# pwm-tl494.net
KiCad netlist of a schematic drawn in Altium Designer
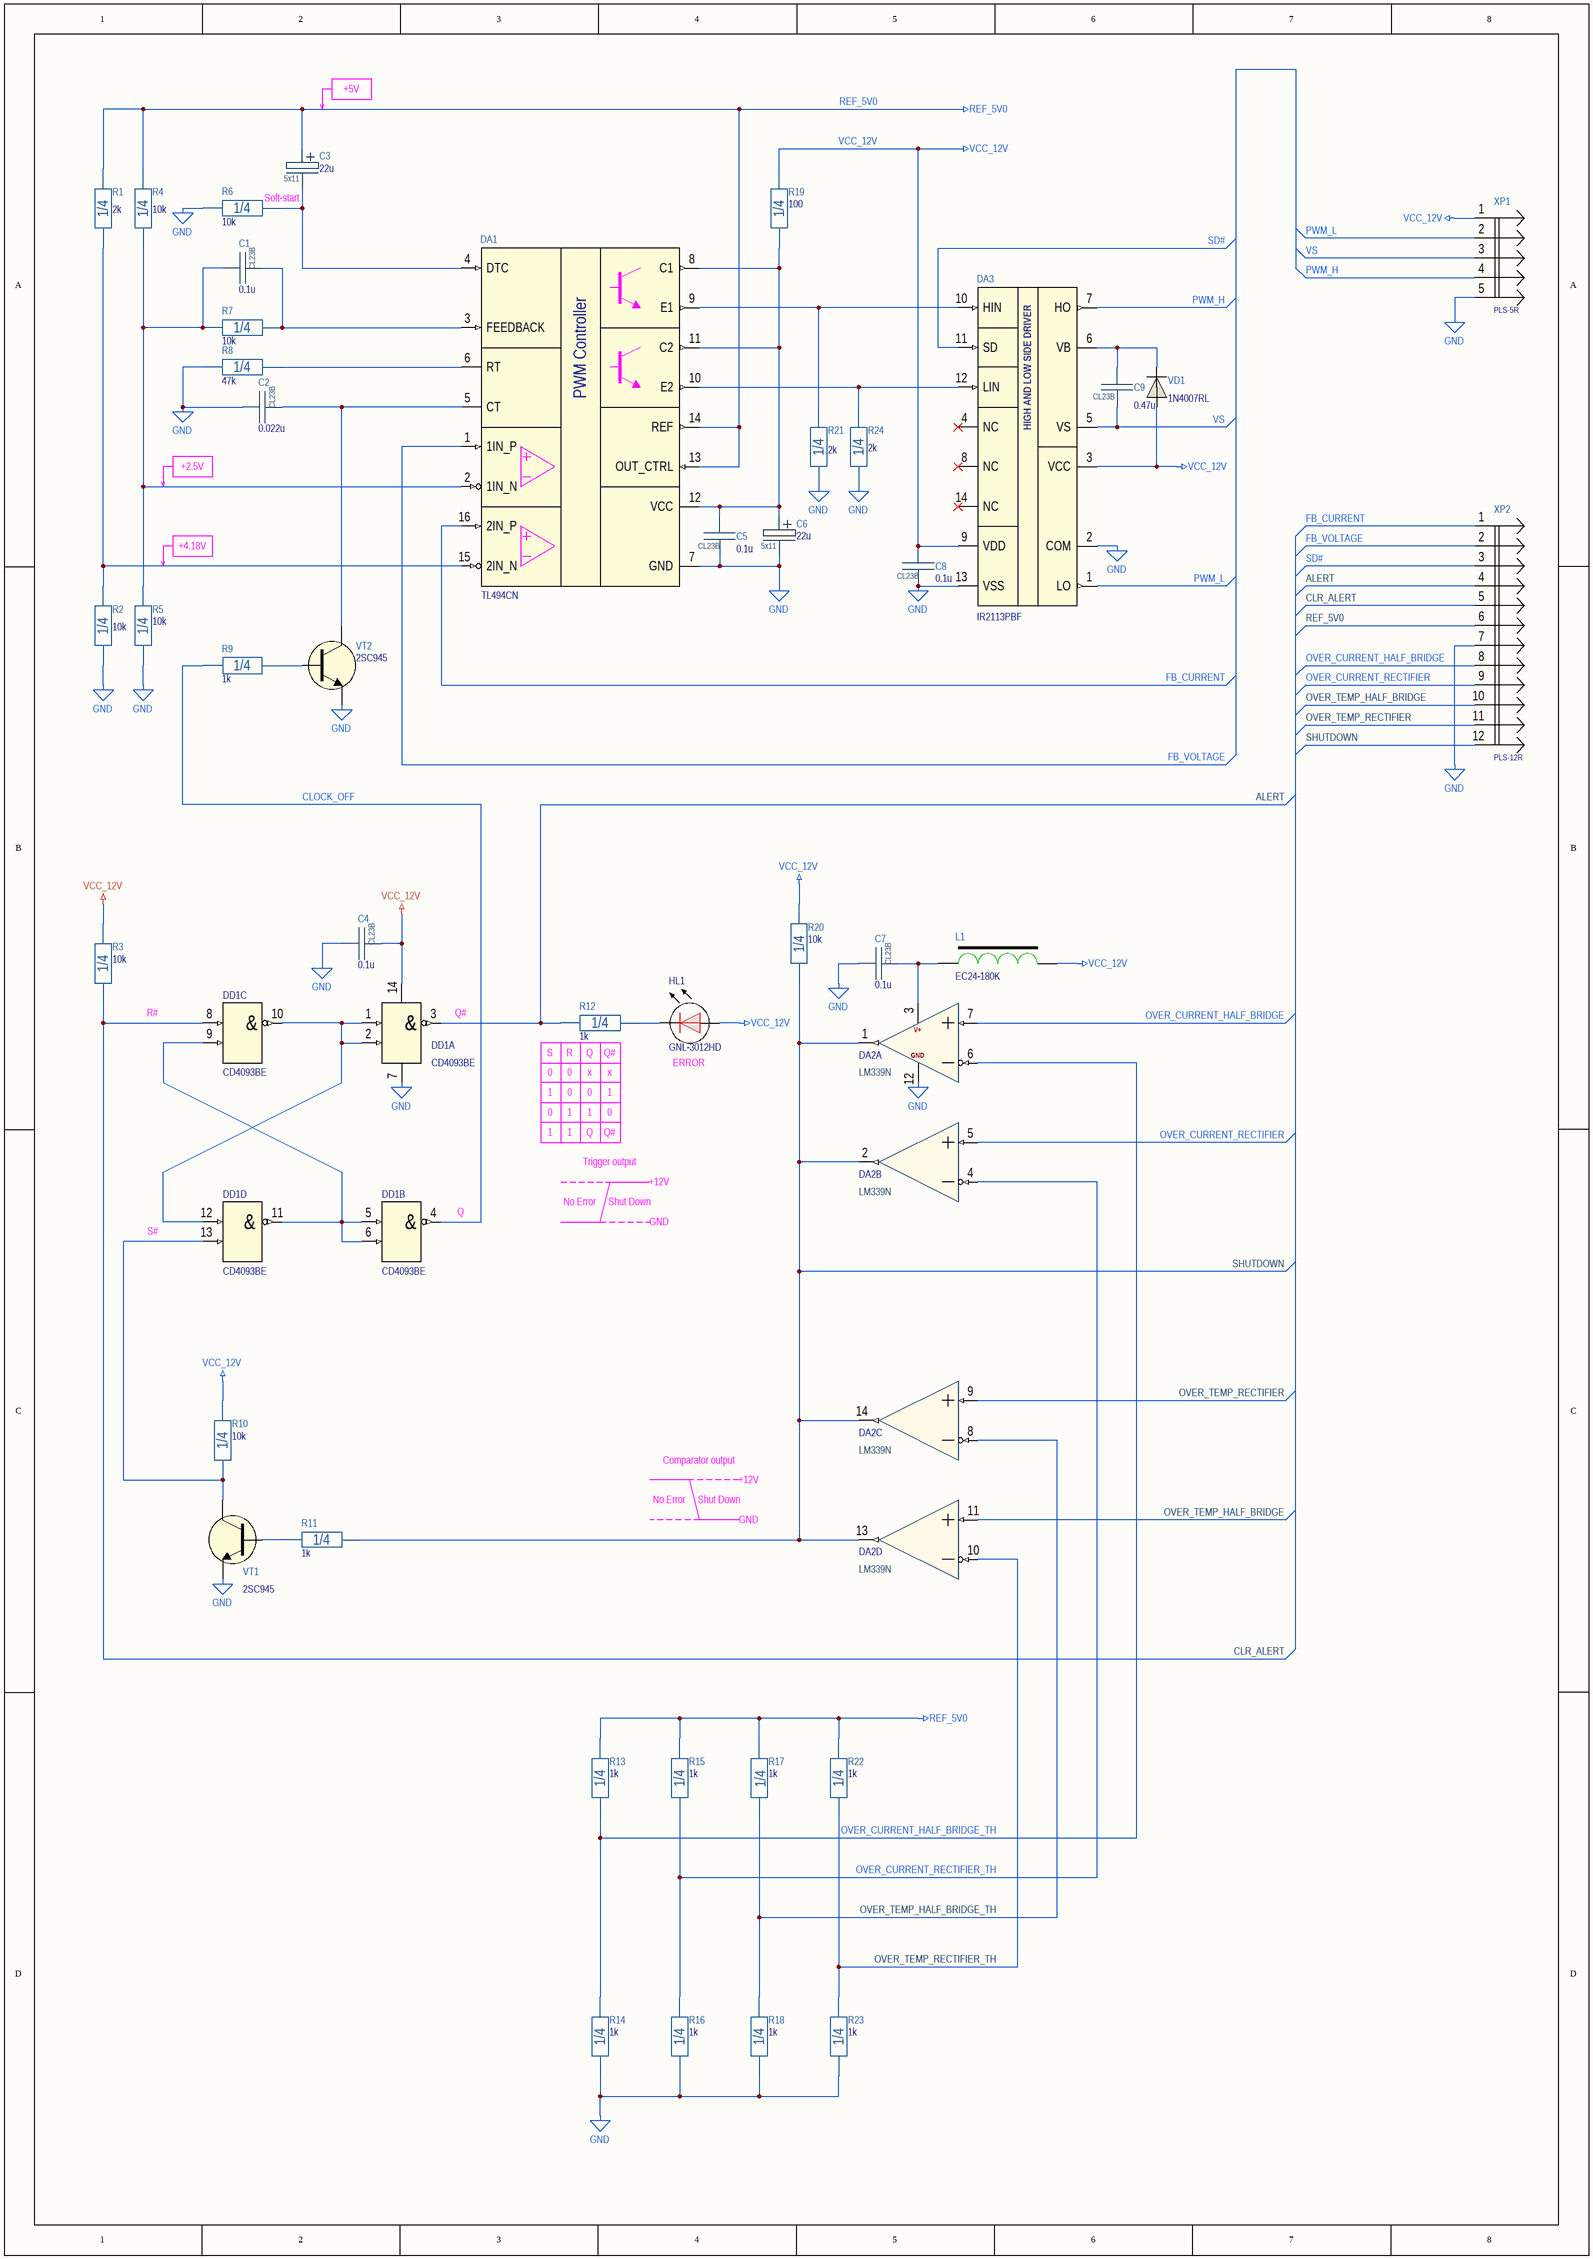
[diagram p0: pwm-tl494.SchDoc]

(export (version "E")
  (design (tool "Eeschema 10.0.6"))
  (components
    (comp (ref "C1")
      (value "0.1u")
      (footprint "PcbLib_RC:CL23B_7.2x2.5")
      (description "Box-type metallized polyester film capacitor")
      (fields
        (field (name "TOLERANCE") "± * %")
        (field (name "VOLTAGE") "63V")
        (field (name "PACKAGE") "CL23B")
      )
      (libsource (lib "Schlib_RC") (part "CL23B"))
    )
    (comp (ref "C2")
      (value "0.022u")
      (footprint "PcbLib_RC:CL23B_7.2x2.5")
      (description "Box-type metallized polyester film capacitor")
      (fields
        (field (name "TOLERANCE") "± * %")
        (field (name "VOLTAGE") "63V")
        (field (name "PACKAGE") "CL23B")
      )
      (libsource (lib "Schlib_RC") (part "CL23B"))
    )
    (comp (ref "C3")
      (value "22u")
      (footprint "PcbLib_RC:ECAP5X11X2.0_BRW")
      (description "Aluminium capacitor")
      (fields
        (field (name "TOLERANCE") "± 20 %")
        (field (name "VOLTAGE") "63V")
        (field (name "PACKAGE") "5x11")
      )
      (libsource (lib "Schlib_RC") (part "C_ECAP"))
    )
    (comp (ref "C4")
      (value "0.1u")
      (footprint "PcbLib_RC:CL23B_7.2x2.5")
      (description "Box-type metallized polyester film capacitor")
      (fields
        (field (name "TOLERANCE") "± * %")
        (field (name "VOLTAGE") "63V")
        (field (name "PACKAGE") "CL23B")
      )
      (libsource (lib "Schlib_RC") (part "CL23B"))
    )
    (comp (ref "C5")
      (value "0.1u")
      (footprint "PcbLib_RC:CL23B_7.2x2.5")
      (description "Box-type metallized polyester film capacitor")
      (fields
        (field (name "TOLERANCE") "± * %")
        (field (name "VOLTAGE") "63V")
        (field (name "PACKAGE") "CL23B")
      )
      (libsource (lib "Schlib_RC") (part "CL23B"))
    )
    (comp (ref "C6")
      (value "22u")
      (footprint "PcbLib_RC:ECAP5X11X2.0_BRW")
      (description "Aluminium capacitor")
      (fields
        (field (name "TOLERANCE") "± 20 %")
        (field (name "VOLTAGE") "63V")
        (field (name "PACKAGE") "5x11")
      )
      (libsource (lib "Schlib_RC") (part "C_ECAP"))
    )
    (comp (ref "C7")
      (value "0.1u")
      (footprint "PcbLib_RC:CL23B_7.2x2.5")
      (description "Box-type metallized polyester film capacitor")
      (fields
        (field (name "TOLERANCE") "± * %")
        (field (name "VOLTAGE") "63V")
        (field (name "PACKAGE") "CL23B")
      )
      (libsource (lib "Schlib_RC") (part "CL23B"))
    )
    (comp (ref "C8")
      (value "0.1u")
      (footprint "PcbLib_RC:CL23B_7.2x2.5")
      (description "Box-type metallized polyester film capacitor")
      (fields
        (field (name "TOLERANCE") "± * %")
        (field (name "VOLTAGE") "63V")
        (field (name "PACKAGE") "CL23B")
      )
      (libsource (lib "Schlib_RC") (part "CL23B"))
    )
    (comp (ref "C9")
      (value "0.47u")
      (footprint "PcbLib_RC:CL23B_7.2x3.5")
      (description "Box-type metallized polyester film capacitor")
      (fields
        (field (name "TOLERANCE") "± * %")
        (field (name "VOLTAGE") "63V")
        (field (name "PACKAGE") "CL23B")
      )
      (libsource (lib "Schlib_RC") (part "CL23B"))
    )
    (comp (ref "DA1")
      (value "TL494CN")
      (footprint "PcbLib_ICs:DIP-16P-M03")
      (description "Pulse-Width-Modulation Control Circuits")
      (fields (field (name "MANUFACTURER") "Texas Instruments"))
      (libsource (lib "Schlib_Texas_Instruments") (part "TL494CN"))
    )
    (comp (ref "DA2")
      (value "LM339N")
      (footprint "PcbLib_ICs:DIP-14P-M02")
      (description "Quad Comparators")
      (fields (field (name "MANUFACTURER") "Texas Instruments"))
      (libsource (lib "Schlib_Texas_Instruments") (part "LM339N"))
    )
    (comp (ref "DA3")
      (value "IR2113PBF")
      (footprint "PcbLib_ICs:DIP-14P-M02")
      (description "HIGH AND LOW SIDE DRIVER")
      (fields (field (name "MANUFACTURER") "International Rectifier"))
      (libsource (lib "Schlib_Infineon") (part "IR2113PBF"))
    )
    (comp (ref "DD1")
      (value "CD4093BE")
      (footprint "PcbLib_ICs:DIP-14P-M02")
      (description "Quad 2-Input NAND Gate Schmitt Triggers")
      (fields (field (name "MANUFACTURER") "Texas Instruments"))
      (libsource (lib "Schlib_Texas_Instruments") (part "CD4093BE"))
    )
    (comp (ref "HL1")
      (value "GNL-3012HD")
      (footprint "PcbLib_Discrete:GNL-3012HD")
      (description "Standard Brightness 3mm LED")
      (fields (field (name "MANUFACTURER") "G-Nor Optoelectronics"))
      (libsource (lib "Schlib_OtherComponents") (part "GNL-3012HD"))
    )
    (comp (ref "L1")
      (value "EC24-180K")
      (footprint "PcbLib_RC:EC24_GREEN_VERT")
      (description "Axial leaded coated inductors")
      (fields (field (name "MANUFACTURER") "3L Electronic"))
      (libsource (lib "Schlib_RC") (part "EC24"))
    )
    (comp (ref "R1")
      (value "2k")
      (footprint "PcbLib_RC:CFR-25(VERTICAL)")
      (description "Resistor 1/4W")
      (fields
        (field (name "TOLERANCE") "± 1 %")
        (field (name "PART NUMBER") "MFR-25FTF52-2K")
        (field (name "PACKAGE") "1/4")
      )
      (libsource (lib "Schlib_RC") (part "CF25"))
    )
    (comp (ref "R2")
      (value "10k")
      (footprint "PcbLib_RC:CFR-25(VERTICAL)")
      (description "Resistor 1/4W")
      (fields
        (field (name "TOLERANCE") "± 1 %")
        (field (name "PART NUMBER") "MFR-25FTF52-10K")
        (field (name "PACKAGE") "1/4")
      )
      (libsource (lib "Schlib_RC") (part "CF25"))
    )
    (comp (ref "R3")
      (value "10k")
      (footprint "PcbLib_RC:CFR-25")
      (description "Resistor 1/4W")
      (fields
        (field (name "TOLERANCE") "± 1 %")
        (field (name "PART NUMBER") "MFR-25FTF52-10K")
        (field (name "PACKAGE") "1/4")
      )
      (libsource (lib "Schlib_RC") (part "CF25"))
    )
    (comp (ref "R4")
      (value "10k")
      (footprint "PcbLib_RC:CFR-25(VERTICAL)")
      (description "Resistor 1/4W")
      (fields
        (field (name "TOLERANCE") "± 1 %")
        (field (name "PART NUMBER") "MFR-25FTF52-10K")
        (field (name "PACKAGE") "1/4")
      )
      (libsource (lib "Schlib_RC") (part "CF25"))
    )
    (comp (ref "R5")
      (value "10k")
      (footprint "PcbLib_RC:CFR-25(VERTICAL)")
      (description "Resistor 1/4W")
      (fields
        (field (name "TOLERANCE") "± 1 %")
        (field (name "PART NUMBER") "MFR-25FTF52-10K")
        (field (name "PACKAGE") "1/4")
      )
      (libsource (lib "Schlib_RC") (part "CF25"))
    )
    (comp (ref "R6")
      (value "10k")
      (footprint "PcbLib_RC:CFR-25(VERTICAL)")
      (description "Resistor 1/4W")
      (fields
        (field (name "TOLERANCE") "± 1 %")
        (field (name "PART NUMBER") "MFR-25FTF52-10K")
        (field (name "PACKAGE") "1/4")
      )
      (libsource (lib "Schlib_RC") (part "CF25"))
    )
    (comp (ref "R7")
      (value "10k")
      (footprint "PcbLib_RC:CFR-25(VERTICAL)")
      (description "Resistor 1/4W")
      (fields
        (field (name "TOLERANCE") "± 1 %")
        (field (name "PART NUMBER") "MFR-25FTF52-10K")
        (field (name "PACKAGE") "1/4")
      )
      (libsource (lib "Schlib_RC") (part "CF25"))
    )
    (comp (ref "R8")
      (value "47k")
      (footprint "PcbLib_RC:CFR-25(VERTICAL)")
      (description "Resistor 1/4W")
      (fields
        (field (name "TOLERANCE") "± 1 %")
        (field (name "PART NUMBER") "MFR-25FTF52-47K")
        (field (name "PACKAGE") "1/4")
      )
      (libsource (lib "Schlib_RC") (part "CF25"))
    )
    (comp (ref "R9")
      (value "1k")
      (footprint "PcbLib_RC:CFR-25(VERTICAL)")
      (description "Resistor 1/4W")
      (fields
        (field (name "TOLERANCE") "± 1 %")
        (field (name "PART NUMBER") "MFR-25FTF52-1K")
        (field (name "PACKAGE") "1/4")
      )
      (libsource (lib "Schlib_RC") (part "CF25"))
    )
    (comp (ref "R10")
      (value "10k")
      (footprint "PcbLib_RC:CFR-25")
      (description "Resistor 1/4W")
      (fields
        (field (name "TOLERANCE") "± 1 %")
        (field (name "PART NUMBER") "MFR-25FTF52-10K")
        (field (name "PACKAGE") "1/4")
      )
      (libsource (lib "Schlib_RC") (part "CF25"))
    )
    (comp (ref "R11")
      (value "1k")
      (footprint "PcbLib_RC:CFR-25(VERTICAL)")
      (description "Resistor 1/4W")
      (fields
        (field (name "TOLERANCE") "± 1 %")
        (field (name "PART NUMBER") "MFR-25FTF52-1K")
        (field (name "PACKAGE") "1/4")
      )
      (libsource (lib "Schlib_RC") (part "CF25"))
    )
    (comp (ref "R12")
      (value "1k")
      (footprint "PcbLib_RC:CFR-25(VERTICAL)")
      (description "Resistor 1/4W")
      (fields
        (field (name "TOLERANCE") "± 1 %")
        (field (name "PART NUMBER") "MFR-25FTF52-1K")
        (field (name "PACKAGE") "1/4")
      )
      (libsource (lib "Schlib_RC") (part "CF25"))
    )
    (comp (ref "R13")
      (value "1k")
      (footprint "PcbLib_RC:CFR-25(VERTICAL)")
      (description "Resistor 1/4W")
      (fields
        (field (name "TOLERANCE") "± 1 %")
        (field (name "PART NUMBER") "MFR-25FTF52-1K")
        (field (name "PACKAGE") "1/4")
      )
      (libsource (lib "Schlib_RC") (part "CF25"))
    )
    (comp (ref "R14")
      (value "1k")
      (footprint "PcbLib_RC:CFR-25(VERTICAL)")
      (description "Resistor 1/4W")
      (fields
        (field (name "TOLERANCE") "± 1 %")
        (field (name "PART NUMBER") "MFR-25FTF52-1K")
        (field (name "PACKAGE") "1/4")
      )
      (libsource (lib "Schlib_RC") (part "CF25"))
    )
    (comp (ref "R15")
      (value "1k")
      (footprint "PcbLib_RC:CFR-25(VERTICAL)")
      (description "Resistor 1/4W")
      (fields
        (field (name "TOLERANCE") "± 1 %")
        (field (name "PART NUMBER") "MFR-25FTF52-1K")
        (field (name "PACKAGE") "1/4")
      )
      (libsource (lib "Schlib_RC") (part "CF25"))
    )
    (comp (ref "R16")
      (value "1k")
      (footprint "PcbLib_RC:CFR-25(VERTICAL)")
      (description "Resistor 1/4W")
      (fields
        (field (name "TOLERANCE") "± 1 %")
        (field (name "PART NUMBER") "MFR-25FTF52-1K")
        (field (name "PACKAGE") "1/4")
      )
      (libsource (lib "Schlib_RC") (part "CF25"))
    )
    (comp (ref "R17")
      (value "1k")
      (footprint "PcbLib_RC:CFR-25(VERTICAL)")
      (description "Resistor 1/4W")
      (fields
        (field (name "TOLERANCE") "± 1 %")
        (field (name "PART NUMBER") "MFR-25FTF52-1K")
        (field (name "PACKAGE") "1/4")
      )
      (libsource (lib "Schlib_RC") (part "CF25"))
    )
    (comp (ref "R18")
      (value "1k")
      (footprint "PcbLib_RC:CFR-25(VERTICAL)")
      (description "Resistor 1/4W")
      (fields
        (field (name "TOLERANCE") "± 1 %")
        (field (name "PART NUMBER") "MFR-25FTF52-1K")
        (field (name "PACKAGE") "1/4")
      )
      (libsource (lib "Schlib_RC") (part "CF25"))
    )
    (comp (ref "R19")
      (value "100")
      (footprint "PcbLib_RC:CFR-25(VERTICAL)")
      (description "Resistor 1/4W")
      (fields
        (field (name "TOLERANCE") "± 1 %")
        (field (name "PART NUMBER") "MFR-25FTF52-100R")
        (field (name "PACKAGE") "1/4")
      )
      (libsource (lib "Schlib_RC") (part "CF25"))
    )
    (comp (ref "R20")
      (value "10k")
      (footprint "PcbLib_RC:CFR-25(VERTICAL)")
      (description "Resistor 1/4W")
      (fields
        (field (name "TOLERANCE") "± 1 %")
        (field (name "PART NUMBER") "MFR-25FTF52-10K")
        (field (name "PACKAGE") "1/4")
      )
      (libsource (lib "Schlib_RC") (part "CF25"))
    )
    (comp (ref "R21")
      (value "2k")
      (footprint "PcbLib_RC:CFR-25")
      (description "Resistor 1/4W")
      (fields
        (field (name "TOLERANCE") "± 1 %")
        (field (name "PART NUMBER") "MFR-25FTF52-2K")
        (field (name "PACKAGE") "1/4")
      )
      (libsource (lib "Schlib_RC") (part "CF25"))
    )
    (comp (ref "R22")
      (value "1k")
      (footprint "PcbLib_RC:CFR-25(VERTICAL)")
      (description "Resistor 1/4W")
      (fields
        (field (name "TOLERANCE") "± 1 %")
        (field (name "PART NUMBER") "MFR-25FTF52-1K")
        (field (name "PACKAGE") "1/4")
      )
      (libsource (lib "Schlib_RC") (part "CF25"))
    )
    (comp (ref "R23")
      (value "1k")
      (footprint "PcbLib_RC:CFR-25(VERTICAL)")
      (description "Resistor 1/4W")
      (fields
        (field (name "TOLERANCE") "± 1 %")
        (field (name "PART NUMBER") "MFR-25FTF52-1K")
        (field (name "PACKAGE") "1/4")
      )
      (libsource (lib "Schlib_RC") (part "CF25"))
    )
    (comp (ref "R24")
      (value "2k")
      (footprint "PcbLib_RC:CFR-25")
      (description "Resistor 1/4W")
      (fields
        (field (name "TOLERANCE") "± 1 %")
        (field (name "PART NUMBER") "MFR-25FTF52-2K")
        (field (name "PACKAGE") "1/4")
      )
      (libsource (lib "Schlib_RC") (part "CF25"))
    )
    (comp (ref "VD1")
      (value "1N4007RL")
      (footprint "PcbLib_Discrete:DO-41")
      (description "1A 1000V Standard Recovery Rectifiers Diode")
      (fields (field (name "MANUFACTURER") "ON Semiconductor"))
      (libsource (lib "Schlib_ONSemiconductor") (part "1N4007RL"))
    )
    (comp (ref "VT1")
      (value "2SC945")
      (footprint "PcbLib_ICs:TO-92 (VERTICAL,LINE)")
      (description "General Purpose n-p-n Transistors")
      (fields (field (name "MANUFACTURER") "NEC"))
      (libsource (lib "Schlib_NEC") (part "2SC945"))
    )
    (comp (ref "VT2")
      (value "2SC945")
      (footprint "PcbLib_ICs:TO-92 (VERTICAL,LINE)")
      (description "General Purpose n-p-n Transistors")
      (fields (field (name "MANUFACTURER") "NEC"))
      (libsource (lib "Schlib_NEC") (part "2SC945"))
    )
    (comp (ref "XP1")
      (value "PLS-5R")
      (footprint "PcbLib_Pin_Headers:PLS-5R")
      (libsource (lib "Schlib_Pin_Headers") (part "PLS-5R"))
    )
    (comp (ref "XP2")
      (value "PLS-12R")
      (footprint "PcbLib_Pin_Headers:PLS-12R")
      (libsource (lib "Schlib_Pin_Headers") (part "PLS-12R"))
    )
  )
  (nets
    (net (code "1") (name "/ALERT") (class "Default")
      (node (ref "DD1") (pin "3") (pinfunction "Y0_3") (pintype "output"))
      (node (ref "R12") (pin "1") (pinfunction "1_1") (pintype "passive"))
      (node (ref "XP2") (pin "4") (pinfunction "4_4") (pintype "passive"))
    )
    (net (code "2") (name "/CLOCK_OFF") (class "Default")
      (node (ref "DD1") (pin "4") (pinfunction "Y1_4") (pintype "output"))
      (node (ref "R9") (pin "1") (pinfunction "1_1") (pintype "passive"))
    )
    (net (code "3") (name "/CLR_ALERT") (class "Default")
      (node (ref "DD1") (pin "8") (pinfunction "A2_8") (pintype "input"))
      (node (ref "R3") (pin "1") (pinfunction "1_1") (pintype "passive"))
      (node (ref "XP2") (pin "5") (pinfunction "5_5") (pintype "passive"))
    )
    (net (code "4") (name "/FB_CURRENT") (class "Default")
      (node (ref "DA1") (pin "16") (pinfunction "2IN_P_16") (pintype "input"))
      (node (ref "XP2") (pin "1") (pinfunction "1_1") (pintype "passive"))
    )
    (net (code "5") (name "/FB_VOLTAGE") (class "Default")
      (node (ref "DA1") (pin "1") (pinfunction "1IN_P_1") (pintype "input"))
      (node (ref "XP2") (pin "2") (pinfunction "2_2") (pintype "passive"))
    )
    (net (code "6") (name "/OVER_CURRENT_HALF_BRIDGE") (class "Default")
      (node (ref "DA2") (pin "7") (pinfunction "1IN+_7") (pintype "input"))
      (node (ref "XP2") (pin "8") (pinfunction "8_8") (pintype "passive"))
    )
    (net (code "7") (name "/OVER_CURRENT_HALF_BRIDGE_TH") (class "Default")
      (node (ref "DA2") (pin "6") (pinfunction "1IN-_6") (pintype "input"))
      (node (ref "R13") (pin "2") (pinfunction "2_2") (pintype "passive"))
      (node (ref "R14") (pin "2") (pinfunction "2_2") (pintype "passive"))
    )
    (net (code "8") (name "/OVER_CURRENT_RECTIFIER") (class "Default")
      (node (ref "DA2") (pin "5") (pinfunction "2IN+_5") (pintype "input"))
      (node (ref "XP2") (pin "9") (pinfunction "9_9") (pintype "passive"))
    )
    (net (code "9") (name "/OVER_CURRENT_RECTIFIER_TH") (class "Default")
      (node (ref "DA2") (pin "4") (pinfunction "2IN-_4") (pintype "input"))
      (node (ref "R15") (pin "1") (pinfunction "1_1") (pintype "passive"))
      (node (ref "R16") (pin "2") (pinfunction "2_2") (pintype "passive"))
    )
    (net (code "10") (name "/OVER_TEMP_HALF_BRIDGE") (class "Default")
      (node (ref "DA2") (pin "11") (pinfunction "4IN+_11") (pintype "input"))
      (node (ref "XP2") (pin "10") (pinfunction "10_10") (pintype "passive"))
    )
    (net (code "11") (name "/OVER_TEMP_HALF_BRIDGE_TH") (class "Default")
      (node (ref "DA2") (pin "8") (pinfunction "3IN-_8") (pintype "input"))
      (node (ref "R17") (pin "2") (pinfunction "2_2") (pintype "passive"))
      (node (ref "R18") (pin "1") (pinfunction "1_1") (pintype "passive"))
    )
    (net (code "12") (name "/OVER_TEMP_RECTIFIER") (class "Default")
      (node (ref "DA2") (pin "9") (pinfunction "3IN+_9") (pintype "input"))
      (node (ref "XP2") (pin "11") (pinfunction "11_11") (pintype "passive"))
    )
    (net (code "13") (name "/OVER_TEMP_RECTIFIER_TH") (class "Default")
      (node (ref "DA2") (pin "10") (pinfunction "4IN-_10") (pintype "input"))
      (node (ref "R22") (pin "1") (pinfunction "1_1") (pintype "passive"))
      (node (ref "R23") (pin "2") (pinfunction "2_2") (pintype "passive"))
    )
    (net (code "14") (name "/PWM_H") (class "Default")
      (node (ref "DA3") (pin "7") (pinfunction "HO_7") (pintype "output"))
      (node (ref "XP1") (pin "4") (pinfunction "4_4") (pintype "passive"))
    )
    (net (code "15") (name "/PWM_L") (class "Default")
      (node (ref "DA3") (pin "1") (pinfunction "LO_1") (pintype "output"))
      (node (ref "XP1") (pin "2") (pinfunction "2_2") (pintype "passive"))
    )
    (net (code "16") (name "/SD#") (class "Default")
      (node (ref "DA3") (pin "11") (pinfunction "SD_11") (pintype "input"))
      (node (ref "XP2") (pin "3") (pinfunction "3_3") (pintype "passive"))
    )
    (net (code "17") (name "/SHUTDOWN") (class "Default")
      (node (ref "DA2") (pin "1") (pinfunction "1OUT_1") (pintype "output"))
      (node (ref "DA2") (pin "13") (pinfunction "4OUT_13") (pintype "output"))
      (node (ref "DA2") (pin "14") (pinfunction "3OUT_14") (pintype "output"))
      (node (ref "DA2") (pin "2") (pinfunction "2OUT_2") (pintype "output"))
      (node (ref "R11") (pin "1") (pinfunction "1_1") (pintype "passive"))
      (node (ref "R20") (pin "1") (pinfunction "1_1") (pintype "passive"))
      (node (ref "XP2") (pin "12") (pinfunction "12_12") (pintype "passive"))
    )
    (net (code "18") (name "/VS") (class "Default")
      (node (ref "C9") (pin "1") (pinfunction "1_1") (pintype "passive"))
      (node (ref "DA3") (pin "5") (pinfunction "VS_5") (pintype "power_in"))
      (node (ref "XP1") (pin "3") (pinfunction "3_3") (pintype "passive"))
    )
    (net (code "19") (name "GND") (class "Default")
      (node (ref "C2") (pin "2") (pinfunction "2_2") (pintype "passive"))
      (node (ref "C4") (pin "2") (pinfunction "2_2") (pintype "passive"))
      (node (ref "C5") (pin "1") (pinfunction "1_1") (pintype "passive"))
      (node (ref "C6") (pin "2") (pinfunction "2_2") (pintype "passive"))
      (node (ref "C7") (pin "2") (pinfunction "2_2") (pintype "passive"))
      (node (ref "C8") (pin "1") (pinfunction "1_1") (pintype "passive"))
      (node (ref "DA1") (pin "7") (pinfunction "GND_7") (pintype "power_in"))
      (node (ref "DA2") (pin "12") (pinfunction "GND_12") (pintype "power_in"))
      (node (ref "DA3") (pin "13") (pinfunction "VSS_13") (pintype "power_in"))
      (node (ref "DA3") (pin "2") (pinfunction "COM_2") (pintype "power_in"))
      (node (ref "DD1") (pin "7") (pinfunction "GND_7") (pintype "power_in"))
      (node (ref "R14") (pin "1") (pinfunction "1_1") (pintype "passive"))
      (node (ref "R16") (pin "1") (pinfunction "1_1") (pintype "passive"))
      (node (ref "R18") (pin "2") (pinfunction "2_2") (pintype "passive"))
      (node (ref "R2") (pin "2") (pinfunction "2_2") (pintype "passive"))
      (node (ref "R21") (pin "1") (pinfunction "1_1") (pintype "passive"))
      (node (ref "R23") (pin "1") (pinfunction "1_1") (pintype "passive"))
      (node (ref "R24") (pin "2") (pinfunction "2_2") (pintype "passive"))
      (node (ref "R5") (pin "1") (pinfunction "1_1") (pintype "passive"))
      (node (ref "R6") (pin "1") (pinfunction "1_1") (pintype "passive"))
      (node (ref "R8") (pin "1") (pinfunction "1_1") (pintype "passive"))
      (node (ref "VT1") (pin "3") (pinfunction "E_3") (pintype "passive"))
      (node (ref "VT2") (pin "3") (pinfunction "E_3") (pintype "passive"))
      (node (ref "XP1") (pin "5") (pinfunction "5_5") (pintype "passive"))
      (node (ref "XP2") (pin "7") (pinfunction "7_7") (pintype "passive"))
    )
    (net (code "20") (name "Net-(DA1-1IN_N)") (class "Default")
      (node (ref "C1") (pin "2") (pinfunction "2_2") (pintype "passive"))
      (node (ref "DA1") (pin "2") (pinfunction "1IN_N_2") (pintype "input"))
      (node (ref "R4") (pin "2") (pinfunction "2_2") (pintype "passive"))
      (node (ref "R5") (pin "2") (pinfunction "2_2") (pintype "passive"))
      (node (ref "R7") (pin "1") (pinfunction "1_1") (pintype "passive"))
    )
    (net (code "21") (name "Net-(DA1-2IN_N)") (class "Default")
      (node (ref "DA1") (pin "15") (pinfunction "2IN_N_15") (pintype "input"))
      (node (ref "R1") (pin "2") (pinfunction "2_2") (pintype "passive"))
      (node (ref "R2") (pin "1") (pinfunction "1_1") (pintype "passive"))
    )
    (net (code "22") (name "Net-(DA1-C1)") (class "Default")
      (node (ref "C5") (pin "2") (pinfunction "2_2") (pintype "passive"))
      (node (ref "C6") (pin "1") (pinfunction "1_1") (pintype "passive"))
      (node (ref "DA1") (pin "11") (pinfunction "C2_11") (pintype "output"))
      (node (ref "DA1") (pin "12") (pinfunction "VCC_12") (pintype "power_in"))
      (node (ref "DA1") (pin "8") (pinfunction "C1_8") (pintype "output"))
      (node (ref "R19") (pin "1") (pinfunction "1_1") (pintype "passive"))
    )
    (net (code "23") (name "Net-(DA1-CT)") (class "Default")
      (node (ref "C2") (pin "1") (pinfunction "1_1") (pintype "passive"))
      (node (ref "DA1") (pin "5") (pinfunction "CT_5") (pintype "passive"))
      (node (ref "VT2") (pin "2") (pinfunction "C_2") (pintype "passive"))
    )
    (net (code "24") (name "Net-(DA1-DTC)") (class "Default")
      (node (ref "C3") (pin "2") (pinfunction "2_2") (pintype "passive"))
      (node (ref "DA1") (pin "4") (pinfunction "DTC_4") (pintype "input"))
      (node (ref "R6") (pin "2") (pinfunction "2_2") (pintype "passive"))
    )
    (net (code "25") (name "Net-(DA1-E1)") (class "Default")
      (node (ref "DA1") (pin "9") (pinfunction "E1_9") (pintype "output"))
      (node (ref "DA3") (pin "10") (pinfunction "HIN_10") (pintype "input"))
      (node (ref "R21") (pin "2") (pinfunction "2_2") (pintype "passive"))
    )
    (net (code "26") (name "Net-(DA1-E2)") (class "Default")
      (node (ref "DA1") (pin "10") (pinfunction "E2_10") (pintype "output"))
      (node (ref "DA3") (pin "12") (pinfunction "LIN_12") (pintype "input"))
      (node (ref "R24") (pin "1") (pinfunction "1_1") (pintype "passive"))
    )
    (net (code "27") (name "Net-(DA1-FEEDBACK)") (class "Default")
      (node (ref "C1") (pin "1") (pinfunction "1_1") (pintype "passive"))
      (node (ref "DA1") (pin "3") (pinfunction "FEEDBACK_3") (pintype "input"))
      (node (ref "R7") (pin "2") (pinfunction "2_2") (pintype "passive"))
    )
    (net (code "28") (name "Net-(DA1-RT)") (class "Default")
      (node (ref "DA1") (pin "6") (pinfunction "RT_6") (pintype "passive"))
      (node (ref "R8") (pin "2") (pinfunction "2_2") (pintype "passive"))
    )
    (net (code "29") (name "Net-(DA2A-VCC)") (class "Default")
      (node (ref "C7") (pin "1") (pinfunction "1_1") (pintype "passive"))
      (node (ref "DA2") (pin "3") (pinfunction "VCC_3") (pintype "power_in"))
      (node (ref "L1") (pin "1") (pinfunction "1_1") (pintype "passive"))
    )
    (net (code "30") (name "Net-(DA3-VB)") (class "Default")
      (node (ref "C9") (pin "2") (pinfunction "2_2") (pintype "passive"))
      (node (ref "DA3") (pin "6") (pinfunction "VB_6") (pintype "power_in"))
      (node (ref "VD1") (pin "1") (pinfunction "C_1") (pintype "passive"))
    )
    (net (code "31") (name "Net-(DD1A-A0)") (class "Default")
      (node (ref "DD1") (pin "1") (pinfunction "A0_1") (pintype "input"))
      (node (ref "DD1") (pin "10") (pinfunction "Y2_10") (pintype "output"))
      (node (ref "DD1") (pin "12") (pinfunction "A3_12") (pintype "input"))
      (node (ref "DD1") (pin "2") (pinfunction "B0_2") (pintype "input"))
    )
    (net (code "32") (name "Net-(DD1B-A1)") (class "Default")
      (node (ref "DD1") (pin "11") (pinfunction "Y3_11") (pintype "output"))
      (node (ref "DD1") (pin "5") (pinfunction "A1_5") (pintype "input"))
      (node (ref "DD1") (pin "6") (pinfunction "B1_6") (pintype "input"))
      (node (ref "DD1") (pin "9") (pinfunction "B2_9") (pintype "input"))
    )
    (net (code "33") (name "Net-(DD1D-B3)") (class "Default")
      (node (ref "DD1") (pin "13") (pinfunction "B3_13") (pintype "input"))
      (node (ref "R10") (pin "1") (pinfunction "1_1") (pintype "passive"))
      (node (ref "VT1") (pin "2") (pinfunction "C_2") (pintype "passive"))
    )
    (net (code "34") (name "Net-(HL1-Pad1)") (class "Default")
      (node (ref "HL1") (pin "1") (pinfunction "1_1") (pintype "passive"))
      (node (ref "R12") (pin "2") (pinfunction "2_2") (pintype "passive"))
    )
    (net (code "35") (name "Net-(VT1-B)") (class "Default")
      (node (ref "R11") (pin "2") (pinfunction "2_2") (pintype "passive"))
      (node (ref "VT1") (pin "1") (pinfunction "B_1") (pintype "passive"))
    )
    (net (code "36") (name "Net-(VT2-B)") (class "Default")
      (node (ref "R9") (pin "2") (pinfunction "2_2") (pintype "passive"))
      (node (ref "VT2") (pin "1") (pinfunction "B_1") (pintype "passive"))
    )
    (net (code "37") (name "REF_5V0") (class "Default")
      (node (ref "C3") (pin "1") (pinfunction "1_1") (pintype "passive"))
      (node (ref "DA1") (pin "13") (pinfunction "OUT_CTRL_13") (pintype "input"))
      (node (ref "DA1") (pin "14") (pinfunction "REF_14") (pintype "output"))
      (node (ref "R1") (pin "1") (pinfunction "1_1") (pintype "passive"))
      (node (ref "R13") (pin "1") (pinfunction "1_1") (pintype "passive"))
      (node (ref "R15") (pin "2") (pinfunction "2_2") (pintype "passive"))
      (node (ref "R17") (pin "1") (pinfunction "1_1") (pintype "passive"))
      (node (ref "R22") (pin "2") (pinfunction "2_2") (pintype "passive"))
      (node (ref "R4") (pin "1") (pinfunction "1_1") (pintype "passive"))
      (node (ref "XP2") (pin "6") (pinfunction "6_6") (pintype "passive"))
    )
    (net (code "38") (name "VCC_12V") (class "Default")
      (node (ref "C4") (pin "1") (pinfunction "1_1") (pintype "passive"))
      (node (ref "C8") (pin "2") (pinfunction "2_2") (pintype "passive"))
      (node (ref "DA3") (pin "3") (pinfunction "VCC_3") (pintype "power_in"))
      (node (ref "DA3") (pin "9") (pinfunction "VDD_9") (pintype "power_in"))
      (node (ref "DD1") (pin "14") (pinfunction "VCC_14") (pintype "power_in"))
      (node (ref "HL1") (pin "2") (pinfunction "2_2") (pintype "passive"))
      (node (ref "L1") (pin "2") (pinfunction "2_2") (pintype "passive"))
      (node (ref "R10") (pin "2") (pinfunction "2_2") (pintype "passive"))
      (node (ref "R19") (pin "2") (pinfunction "2_2") (pintype "passive"))
      (node (ref "R20") (pin "2") (pinfunction "2_2") (pintype "passive"))
      (node (ref "R3") (pin "2") (pinfunction "2_2") (pintype "passive"))
      (node (ref "VD1") (pin "2") (pinfunction "A_2") (pintype "passive"))
      (node (ref "XP1") (pin "1") (pinfunction "1_1") (pintype "passive"))
    )
    (net (code "39") (name "unconnected-(DA3-NC-Pad4)") (class "Default")
      (node (ref "DA3") (pin "4") (pinfunction "NC_4") (pintype "tri_state+no_connect"))
    )
    (net (code "40") (name "unconnected-(DA3-NC-Pad8)") (class "Default")
      (node (ref "DA3") (pin "8") (pinfunction "NC_8") (pintype "tri_state+no_connect"))
    )
    (net (code "41") (name "unconnected-(DA3-NC-Pad14)") (class "Default")
      (node (ref "DA3") (pin "14") (pinfunction "NC_14") (pintype "tri_state+no_connect"))
    )
  )
)
